# Schematic_v24.net
KiCad netlist of a schematic drawn in EAGLE
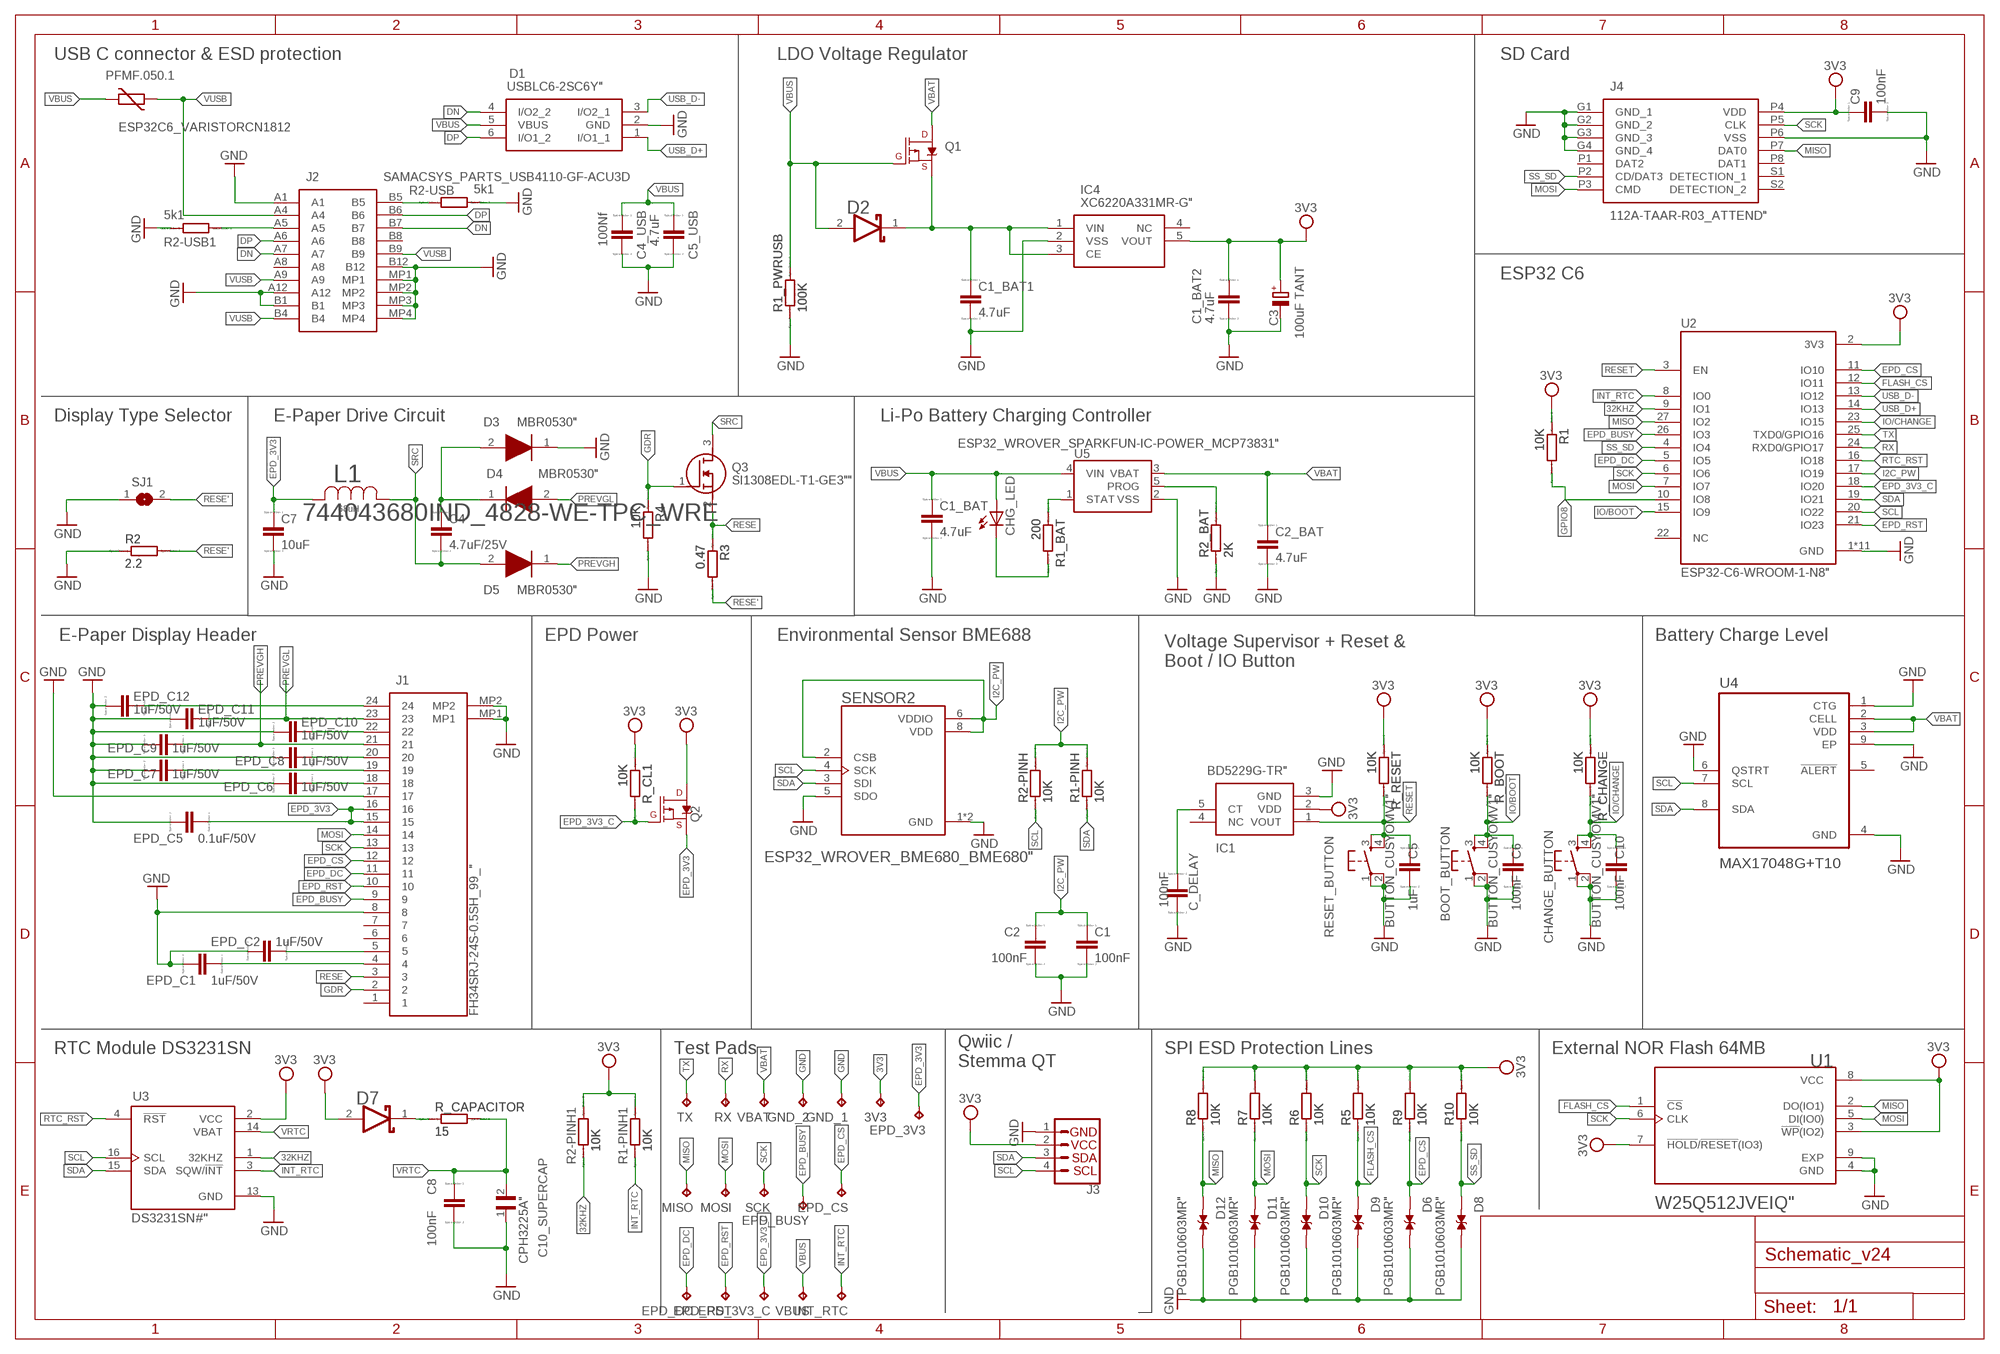
[diagram p0: schematic, sheet 1]

(export (version "E")
  (design (tool "Eeschema 10.0.6"))
  (components
    (comp (ref "3V3")
      (value "TPTP20R")
      (footprint "eagle-import:TP20R")
      (libsource (lib "eagle-import") (part "TPTP20R"))
    )
    (comp (ref "BOOT_BUTTON")
      (value "BUTTON_CUSYOMV1\"")
      (footprint "eagle-import:MYBUTTON")
      (libsource (lib "eagle-import") (part "BUTTON_CUSYOMV1{dblquote}"))
    )
    (comp (ref "C1")
      (value "100nF")
      (footprint "eagle-import:ESP32_WROVER_EAGLE-LTSPICE_C0402")
      (libsource (lib "eagle-import") (part "ESP32_WROVER_EAGLE-LTSPICE_CC0402"))
    )
    (comp (ref "C1_BAT")
      (value "4.7uF")
      (footprint "eagle-import:ESP32_WROVER_EAGLE-LTSPICE_C0402")
      (libsource (lib "eagle-import") (part "ESP32_WROVER_EAGLE-LTSPICE_CC0402"))
    )
    (comp (ref "C1_BAT1")
      (value "4.7uF")
      (footprint "eagle-import:EAGLE-LTSPICE_C0402")
      (libsource (lib "eagle-import") (part "EAGLE-LTSPICE_CC0402"))
    )
    (comp (ref "C1_BAT2")
      (value "4.7uF")
      (footprint "eagle-import:EAGLE-LTSPICE_C0402")
      (libsource (lib "eagle-import") (part "EAGLE-LTSPICE_CC0402"))
    )
    (comp (ref "C2")
      (value "100nF")
      (footprint "eagle-import:ESP32_WROVER_EAGLE-LTSPICE_C0402")
      (libsource (lib "eagle-import") (part "ESP32_WROVER_EAGLE-LTSPICE_CC0402"))
    )
    (comp (ref "C2_BAT")
      (value "4.7uF")
      (footprint "eagle-import:ESP32_WROVER_EAGLE-LTSPICE_C0402")
      (libsource (lib "eagle-import") (part "ESP32_WROVER_EAGLE-LTSPICE_CC0402"))
    )
    (comp (ref "C3")
      (value "100uF TANT")
      (footprint "eagle-import:RCL_CT3528")
      (libsource (lib "eagle-import") (part "RCL_CPOL-EUCT3528"))
    )
    (comp (ref "C4")
      (value "4.7uF/25V")
      (footprint "eagle-import:ESP32_WROVER_EAGLE-LTSPICE_C0402")
      (libsource (lib "eagle-import") (part "ESP32_WROVER_EAGLE-LTSPICE_CC0402"))
    )
    (comp (ref "C4_USB")
      (value "100Nf")
      (footprint "eagle-import:ESP32_WROVER_EAGLE-LTSPICE_C0402")
      (libsource (lib "eagle-import") (part "ESP32_WROVER_EAGLE-LTSPICE_CC0402"))
    )
    (comp (ref "C5")
      (value "1uF")
      (footprint "eagle-import:ESP32_WROVER_EAGLE-LTSPICE_C0402")
      (libsource (lib "eagle-import") (part "ESP32_WROVER_EAGLE-LTSPICE_CC0402"))
    )
    (comp (ref "C5_USB")
      (value "4.7uF")
      (footprint "eagle-import:ESP32_WROVER_EAGLE-LTSPICE_C0402")
      (libsource (lib "eagle-import") (part "ESP32_WROVER_EAGLE-LTSPICE_CC0402"))
    )
    (comp (ref "C6")
      (value "100nF")
      (footprint "eagle-import:ESP32_WROVER_EAGLE-LTSPICE_C0402")
      (libsource (lib "eagle-import") (part "ESP32_WROVER_EAGLE-LTSPICE_CC0402"))
    )
    (comp (ref "C7")
      (value "10uF")
      (footprint "eagle-import:ESP32_WROVER_EAGLE-LTSPICE_C0402")
      (libsource (lib "eagle-import") (part "ESP32_WROVER_EAGLE-LTSPICE_CC0402"))
    )
    (comp (ref "C8")
      (value "100nF")
      (footprint "eagle-import:ESP32_WROVER_EAGLE-LTSPICE_C0402")
      (libsource (lib "eagle-import") (part "ESP32_WROVER_EAGLE-LTSPICE_CC0402"))
    )
    (comp (ref "C9")
      (value "100nF")
      (footprint "eagle-import:EAGLE-LTSPICE_C0402")
      (libsource (lib "eagle-import") (part "EAGLE-LTSPICE_CC0402"))
    )
    (comp (ref "C10")
      (value "100nF")
      (footprint "eagle-import:ESP32_WROVER_EAGLE-LTSPICE_C0402")
      (libsource (lib "eagle-import") (part "ESP32_WROVER_EAGLE-LTSPICE_CC0402"))
    )
    (comp (ref "C10_SUPERCAP")
      (value "CPH3225A\"")
      (footprint "eagle-import:CAPCP3225X100N")
      (libsource (lib "eagle-import") (part "CPH3225A{dblquote}"))
    )
    (comp (ref "CHANGE_BUTTON")
      (value "BUTTON_CUSYOMV1\"")
      (footprint "eagle-import:MYBUTTON")
      (libsource (lib "eagle-import") (part "BUTTON_CUSYOMV1{dblquote}"))
    )
    (comp (ref "CHG_LED")
      (value "ADAFRUIT_LEDCHIP-LED0603")
      (footprint "eagle-import:ADAFRUIT_CHIP-LED0603")
      (libsource (lib "eagle-import") (part "ADAFRUIT_LEDCHIP-LED0603"))
    )
    (comp (ref "C_DELAY")
      (value "100nF")
      (footprint "eagle-import:ESP32_WROVER_EAGLE-LTSPICE_C0402")
      (libsource (lib "eagle-import") (part "ESP32_WROVER_EAGLE-LTSPICE_CC0402"))
    )
    (comp (ref "D1")
      (value "USBLC6-2SC6Y\"")
      (footprint "eagle-import:SOT95P280X145-6N")
      (libsource (lib "eagle-import") (part "USBLC6-2SC6Y{dblquote}"))
    )
    (comp (ref "D2")
      (value "ESP32_WROVER_AVX---SD0805S020S1R0_AVX_SD0805S020S1R0_0_0AVX_SD0805S020S1R0_0_0")
      (footprint "eagle-import:ESP32_WROVER_AVX---SD0805S020S1R0_AVX_SD0805S020S1R0_0")
      (libsource (lib "eagle-import") (part "ESP32_WROVER_AVX---SD0805S020S1R0_AVX_SD0805S020S1R0_0_0AVX_SD0805S020S1R0_0_0"))
    )
    (comp (ref "D3")
      (value "MBR0530\"")
      (footprint "eagle-import:SOD3716X135N")
      (libsource (lib "eagle-import") (part "MBR0530{dblquote}"))
    )
    (comp (ref "D4")
      (value "MBR0530\"")
      (footprint "eagle-import:SOD3716X135N")
      (libsource (lib "eagle-import") (part "MBR0530{dblquote}"))
    )
    (comp (ref "D5")
      (value "MBR0530\"")
      (footprint "eagle-import:SOD3716X135N")
      (libsource (lib "eagle-import") (part "MBR0530{dblquote}"))
    )
    (comp (ref "D6")
      (value "PGB1010603MR\"")
      (footprint "eagle-import:DIOC1608X36N")
      (libsource (lib "eagle-import") (part "PGB1010603MR{dblquote}"))
    )
    (comp (ref "D7")
      (value "ESP32_WROVER_AVX---SD0805S020S1R0_AVX_SD0805S020S1R0_0_0AVX_SD0805S020S1R0_0_0")
      (footprint "eagle-import:ESP32_WROVER_AVX---SD0805S020S1R0_AVX_SD0805S020S1R0_0")
      (libsource (lib "eagle-import") (part "ESP32_WROVER_AVX---SD0805S020S1R0_AVX_SD0805S020S1R0_0_0AVX_SD0805S020S1R0_0_0"))
    )
    (comp (ref "D8")
      (value "PGB1010603MR\"")
      (footprint "eagle-import:DIOC1608X36N")
      (libsource (lib "eagle-import") (part "PGB1010603MR{dblquote}"))
    )
    (comp (ref "D9")
      (value "PGB1010603MR\"")
      (footprint "eagle-import:DIOC1608X36N")
      (libsource (lib "eagle-import") (part "PGB1010603MR{dblquote}"))
    )
    (comp (ref "D10")
      (value "PGB1010603MR\"")
      (footprint "eagle-import:DIOC1608X36N")
      (libsource (lib "eagle-import") (part "PGB1010603MR{dblquote}"))
    )
    (comp (ref "D11")
      (value "PGB1010603MR\"")
      (footprint "eagle-import:DIOC1608X36N")
      (libsource (lib "eagle-import") (part "PGB1010603MR{dblquote}"))
    )
    (comp (ref "D12")
      (value "PGB1010603MR\"")
      (footprint "eagle-import:DIOC1608X36N")
      (libsource (lib "eagle-import") (part "PGB1010603MR{dblquote}"))
    )
    (comp (ref "EPD_3V3")
      (value "TPTP20R")
      (footprint "eagle-import:TP20R")
      (libsource (lib "eagle-import") (part "TPTP20R"))
    )
    (comp (ref "EPD_3V3_C")
      (value "TPTP20R")
      (footprint "eagle-import:TP20R")
      (libsource (lib "eagle-import") (part "TPTP20R"))
    )
    (comp (ref "EPD_BUSY")
      (value "TPTP20R")
      (footprint "eagle-import:TP20R")
      (libsource (lib "eagle-import") (part "TPTP20R"))
    )
    (comp (ref "EPD_C1")
      (value "1uF/50V")
      (footprint "eagle-import:ESP32_WROVER_EAGLE-LTSPICE_C0402")
      (libsource (lib "eagle-import") (part "ESP32_WROVER_EAGLE-LTSPICE_CC0402"))
    )
    (comp (ref "EPD_C2")
      (value "1uF/50V")
      (footprint "eagle-import:ESP32_WROVER_EAGLE-LTSPICE_C0402")
      (libsource (lib "eagle-import") (part "ESP32_WROVER_EAGLE-LTSPICE_CC0402"))
    )
    (comp (ref "EPD_C5")
      (value "0.1uF/50V")
      (footprint "eagle-import:ESP32_WROVER_EAGLE-LTSPICE_C0402")
      (libsource (lib "eagle-import") (part "ESP32_WROVER_EAGLE-LTSPICE_CC0402"))
    )
    (comp (ref "EPD_C6")
      (value "1uF/50V")
      (footprint "eagle-import:ESP32_WROVER_EAGLE-LTSPICE_C0402")
      (libsource (lib "eagle-import") (part "ESP32_WROVER_EAGLE-LTSPICE_CC0402"))
    )
    (comp (ref "EPD_C7")
      (value "1uF/50V")
      (footprint "eagle-import:ESP32_WROVER_EAGLE-LTSPICE_C0402")
      (libsource (lib "eagle-import") (part "ESP32_WROVER_EAGLE-LTSPICE_CC0402"))
    )
    (comp (ref "EPD_C8")
      (value "1uF/50V")
      (footprint "eagle-import:ESP32_WROVER_EAGLE-LTSPICE_C0402")
      (libsource (lib "eagle-import") (part "ESP32_WROVER_EAGLE-LTSPICE_CC0402"))
    )
    (comp (ref "EPD_C9")
      (value "1uF/50V")
      (footprint "eagle-import:ESP32_WROVER_EAGLE-LTSPICE_C0402")
      (libsource (lib "eagle-import") (part "ESP32_WROVER_EAGLE-LTSPICE_CC0402"))
    )
    (comp (ref "EPD_C10")
      (value "1uF/50V")
      (footprint "eagle-import:ESP32_WROVER_EAGLE-LTSPICE_C0402")
      (libsource (lib "eagle-import") (part "ESP32_WROVER_EAGLE-LTSPICE_CC0402"))
    )
    (comp (ref "EPD_C11")
      (value "1uF/50V")
      (footprint "eagle-import:ESP32_WROVER_EAGLE-LTSPICE_C0402")
      (libsource (lib "eagle-import") (part "ESP32_WROVER_EAGLE-LTSPICE_CC0402"))
    )
    (comp (ref "EPD_C12")
      (value "1uF/50V")
      (footprint "eagle-import:ESP32_WROVER_EAGLE-LTSPICE_C0402")
      (libsource (lib "eagle-import") (part "ESP32_WROVER_EAGLE-LTSPICE_CC0402"))
    )
    (comp (ref "EPD_CS")
      (value "TPTP20R")
      (footprint "eagle-import:TP20R")
      (libsource (lib "eagle-import") (part "TPTP20R"))
    )
    (comp (ref "EPD_DC")
      (value "TPTP20R")
      (footprint "eagle-import:TP20R")
      (libsource (lib "eagle-import") (part "TPTP20R"))
    )
    (comp (ref "EPD_RST")
      (value "TPTP20R")
      (footprint "eagle-import:TP20R")
      (libsource (lib "eagle-import") (part "TPTP20R"))
    )
    (comp (ref "GND_1")
      (value "TPTP20R")
      (footprint "eagle-import:TP20R")
      (libsource (lib "eagle-import") (part "TPTP20R"))
    )
    (comp (ref "GND_2")
      (value "TPTP20R")
      (footprint "eagle-import:TP20R")
      (libsource (lib "eagle-import") (part "TPTP20R"))
    )
    (comp (ref "IC1")
      (value "BD5229G-TR\"")
      (footprint "eagle-import:SOT95P280X125-5N")
      (libsource (lib "eagle-import") (part "BD5229G-TR{dblquote}"))
    )
    (comp (ref "IC4")
      (value "XC6220A331MR-G\"")
      (footprint "eagle-import:SOT95P280X120-5N")
      (libsource (lib "eagle-import") (part "XC6220A331MR-G{dblquote}"))
    )
    (comp (ref "INT_RTC")
      (value "TPTP20R")
      (footprint "eagle-import:TP20R")
      (libsource (lib "eagle-import") (part "TPTP20R"))
    )
    (comp (ref "J1")
      (value "FH34SRJ-24S-0.5SH_99_\"")
      (footprint "eagle-import:FH34SRJ24S05SH99")
      (libsource (lib "eagle-import") (part "FH34SRJ-24S-0.5SH_99_{dblquote}"))
    )
    (comp (ref "J2")
      (value "SAMACSYS_PARTS_USB4110-GF-ACU3D")
      (footprint "eagle-import:SAMACSYS_PARTS_USB4110GFA")
      (libsource (lib "eagle-import") (part "SAMACSYS_PARTS_USB4110-GF-ACU3D"))
    )
    (comp (ref "J3")
      (value "QWIIC_RIGHT_ANGLE")
      (footprint "eagle-import:JST04_1MM_RA")
      (libsource (lib "eagle-import") (part "QWIIC_CONNECTORJS-1MM"))
    )
    (comp (ref "J4")
      (value "112A-TAAR-R03_ATTEND\"")
      (footprint "eagle-import:112ATAARR03ATTEND")
      (libsource (lib "eagle-import") (part "112A-TAAR-R03_ATTEND{dblquote}"))
    )
    (comp (ref "L1")
      (value "744043680IND_4828-WE-TPC_WRE")
      (footprint "eagle-import:IND_4828-WE-TPC_WRE")
      (fields (field (name "VAL") "68uH"))
      (libsource (lib "eagle-import") (part "744043680IND_4828-WE-TPC_WRE"))
    )
    (comp (ref "MISO")
      (value "TPTP20R")
      (footprint "eagle-import:TP20R")
      (libsource (lib "eagle-import") (part "TPTP20R"))
    )
    (comp (ref "MOSI")
      (value "TPTP20R")
      (footprint "eagle-import:TP20R")
      (libsource (lib "eagle-import") (part "TPTP20R"))
    )
    (comp (ref "PFMF.050.1")
      (value "ESP32C6_VARISTORCN1812")
      (footprint "eagle-import:ESP32C6_VARISTOR_CT_CN1812")
      (libsource (lib "eagle-import") (part "ESP32C6_VARISTORCN1812"))
    )
    (comp (ref "Q1")
      (value "20V/4.2A/52mΩ/1.4W")
      (footprint "eagle-import:ESP32_WROVER_SPARKFUN-DISCRETESEMI_SOT23-3")
      (libsource (lib "eagle-import") (part "ESP32_WROVER_SPARKFUN-DISCRETESEMI_MOSFET_PCH-DMG2305UX-7"))
    )
    (comp (ref "Q2")
      (value "20V/4.2A/52mΩ/1.4W")
      (footprint "eagle-import:ESP32_WROVER_SPARKFUN-DISCRETESEMI_SOT23-3")
      (libsource (lib "eagle-import") (part "ESP32_WROVER_SPARKFUN-DISCRETESEMI_MOSFET_PCH-DMG2305UX-7"))
    )
    (comp (ref "Q3")
      (value "SI1308EDL-T1-GE3\"\"")
      (footprint "eagle-import:SOT65P210X110-3N")
      (libsource (lib "eagle-import") (part "SI1308EDL-T1-GE3{dblquote}{dblquote}"))
    )
    (comp (ref "R1")
      (value "10K")
      (footprint "eagle-import:ESP32_WROVER_EAGLE-LTSPICE_R0402")
      (libsource (lib "eagle-import") (part "ESP32_WROVER_EAGLE-LTSPICE_RR0402"))
    )
    (comp (ref "R1-PINH")
      (value "10K")
      (footprint "eagle-import:ESP32_WROVER_EAGLE-LTSPICE_R0402")
      (libsource (lib "eagle-import") (part "ESP32_WROVER_EAGLE-LTSPICE_RR0402"))
    )
    (comp (ref "R1-PINH1")
      (value "10K")
      (footprint "eagle-import:ESP32_WROVER_EAGLE-LTSPICE_R0402")
      (libsource (lib "eagle-import") (part "ESP32_WROVER_EAGLE-LTSPICE_RR0402"))
    )
    (comp (ref "R1_BAT")
      (value "200")
      (footprint "eagle-import:ESP32_WROVER_EAGLE-LTSPICE_R0402")
      (libsource (lib "eagle-import") (part "ESP32_WROVER_EAGLE-LTSPICE_RR0402"))
    )
    (comp (ref "R1_PWRUSB")
      (value "100K")
      (footprint "eagle-import:ESP32_WROVER_EAGLE-LTSPICE_R0402")
      (libsource (lib "eagle-import") (part "ESP32_WROVER_EAGLE-LTSPICE_RR0402"))
    )
    (comp (ref "R2")
      (value "2.2")
      (footprint "eagle-import:ESP32_WROVER_EAGLE-LTSPICE_R0402")
      (libsource (lib "eagle-import") (part "ESP32_WROVER_EAGLE-LTSPICE_RR0402"))
    )
    (comp (ref "R2-PINH")
      (value "10K")
      (footprint "eagle-import:ESP32_WROVER_EAGLE-LTSPICE_R0402")
      (libsource (lib "eagle-import") (part "ESP32_WROVER_EAGLE-LTSPICE_RR0402"))
    )
    (comp (ref "R2-PINH1")
      (value "10K")
      (footprint "eagle-import:ESP32_WROVER_EAGLE-LTSPICE_R0402")
      (libsource (lib "eagle-import") (part "ESP32_WROVER_EAGLE-LTSPICE_RR0402"))
    )
    (comp (ref "R2-USB")
      (value "5k1")
      (footprint "eagle-import:ESP32_WROVER_EAGLE-LTSPICE_R0402")
      (libsource (lib "eagle-import") (part "ESP32_WROVER_EAGLE-LTSPICE_RR0402"))
    )
    (comp (ref "R2-USB1")
      (value "5k1")
      (footprint "eagle-import:ESP32_WROVER_EAGLE-LTSPICE_R0402")
      (libsource (lib "eagle-import") (part "ESP32_WROVER_EAGLE-LTSPICE_RR0402"))
    )
    (comp (ref "R2_BAT")
      (value "2K")
      (footprint "eagle-import:ESP32_WROVER_EAGLE-LTSPICE_R0402")
      (libsource (lib "eagle-import") (part "ESP32_WROVER_EAGLE-LTSPICE_RR0402"))
    )
    (comp (ref "R3")
      (value "0.47")
      (footprint "eagle-import:ESP32_WROVER_EAGLE-LTSPICE_R0402")
      (libsource (lib "eagle-import") (part "ESP32_WROVER_EAGLE-LTSPICE_RR0402"))
    )
    (comp (ref "R4")
      (value "10K")
      (footprint "eagle-import:ESP32_WROVER_EAGLE-LTSPICE_R0402")
      (libsource (lib "eagle-import") (part "ESP32_WROVER_EAGLE-LTSPICE_RR0402"))
    )
    (comp (ref "R5")
      (value "10K")
      (footprint "eagle-import:ESP32_WROVER_EAGLE-LTSPICE_R0402")
      (libsource (lib "eagle-import") (part "ESP32_WROVER_EAGLE-LTSPICE_RR0402"))
    )
    (comp (ref "R6")
      (value "10K")
      (footprint "eagle-import:ESP32_WROVER_EAGLE-LTSPICE_R0402")
      (libsource (lib "eagle-import") (part "ESP32_WROVER_EAGLE-LTSPICE_RR0402"))
    )
    (comp (ref "R7")
      (value "10K")
      (footprint "eagle-import:ESP32_WROVER_EAGLE-LTSPICE_R0402")
      (libsource (lib "eagle-import") (part "ESP32_WROVER_EAGLE-LTSPICE_RR0402"))
    )
    (comp (ref "R8")
      (value "10K")
      (footprint "eagle-import:ESP32_WROVER_EAGLE-LTSPICE_R0402")
      (libsource (lib "eagle-import") (part "ESP32_WROVER_EAGLE-LTSPICE_RR0402"))
    )
    (comp (ref "R9")
      (value "10K")
      (footprint "eagle-import:ESP32_WROVER_EAGLE-LTSPICE_R0402")
      (libsource (lib "eagle-import") (part "ESP32_WROVER_EAGLE-LTSPICE_RR0402"))
    )
    (comp (ref "R10")
      (value "10K")
      (footprint "eagle-import:ESP32_WROVER_EAGLE-LTSPICE_R0402")
      (libsource (lib "eagle-import") (part "ESP32_WROVER_EAGLE-LTSPICE_RR0402"))
    )
    (comp (ref "RESET_BUTTON")
      (value "BUTTON_CUSYOMV1\"")
      (footprint "eagle-import:MYBUTTON")
      (libsource (lib "eagle-import") (part "BUTTON_CUSYOMV1{dblquote}"))
    )
    (comp (ref "RX")
      (value "TPTP20R")
      (footprint "eagle-import:TP20R")
      (libsource (lib "eagle-import") (part "TPTP20R"))
    )
    (comp (ref "R_BOOT")
      (value "10K")
      (footprint "eagle-import:ESP32_WROVER_EAGLE-LTSPICE_R0402")
      (libsource (lib "eagle-import") (part "ESP32_WROVER_EAGLE-LTSPICE_RR0402"))
    )
    (comp (ref "R_CAPACITOR")
      (value "15")
      (footprint "eagle-import:ESP32_WROVER_EAGLE-LTSPICE_R0402")
      (libsource (lib "eagle-import") (part "ESP32_WROVER_EAGLE-LTSPICE_RR0402"))
    )
    (comp (ref "R_CHANGE")
      (value "10K")
      (footprint "eagle-import:ESP32_WROVER_EAGLE-LTSPICE_R0402")
      (libsource (lib "eagle-import") (part "ESP32_WROVER_EAGLE-LTSPICE_RR0402"))
    )
    (comp (ref "R_CL1")
      (value "10K")
      (footprint "eagle-import:ESP32_WROVER_EAGLE-LTSPICE_R0402")
      (libsource (lib "eagle-import") (part "ESP32_WROVER_EAGLE-LTSPICE_RR0402"))
    )
    (comp (ref "R_RESET")
      (value "10K")
      (footprint "eagle-import:ESP32_WROVER_EAGLE-LTSPICE_R0402")
      (libsource (lib "eagle-import") (part "ESP32_WROVER_EAGLE-LTSPICE_RR0402"))
    )
    (comp (ref "SCK")
      (value "TPTP20R")
      (footprint "eagle-import:TP20R")
      (libsource (lib "eagle-import") (part "TPTP20R"))
    )
    (comp (ref "SENSOR2")
      (value "ESP32_WROVER_BME680_BME680\"")
      (footprint "eagle-import:ESP32_WROVER_BME680_PSON80P300X300X100-8N")
      (libsource (lib "eagle-import") (part "ESP32_WROVER_BME680_BME680{dblquote}"))
    )
    (comp (ref "SJ1")
      (value "SJ\"\"")
      (footprint "eagle-import:SJ")
      (libsource (lib "eagle-import") (part "SJ{dblquote}{dblquote}"))
    )
    (comp (ref "TX")
      (value "TPTP20R")
      (footprint "eagle-import:TP20R")
      (libsource (lib "eagle-import") (part "TPTP20R"))
    )
    (comp (ref "U1")
      (value "W25Q512JVEIQ\"")
      (footprint "eagle-import:SON127P600X800X80-9N")
      (libsource (lib "eagle-import") (part "W25Q512JVEIQ{dblquote}"))
    )
    (comp (ref "U2")
      (value "ESP32-C6-WROOM-1-N8\"")
      (footprint "eagle-import:XCVR_ESP32-C6-WROOM-1-N8")
      (libsource (lib "eagle-import") (part "ESP32-C6-WROOM-1-N8{dblquote}"))
    )
    (comp (ref "U3")
      (value "DS3231SN#\"")
      (footprint "eagle-import:SOIC127P1032X265-16N")
      (libsource (lib "eagle-import") (part "DS3231SN#{dblquote}"))
    )
    (comp (ref "U4")
      (value "MAX17048G+T10")
      (footprint "eagle-import:SON50P200X200X80-9N")
      (libsource (lib "eagle-import") (part "MAX17048G+T10{dblquote}"))
    )
    (comp (ref "U5")
      (value "ESP32_WROVER_SPARKFUN-IC-POWER_MCP73831\"")
      (footprint "eagle-import:ESP32_WROVER_SPARKFUN-IC-POWER_SOT23-5")
      (libsource (lib "eagle-import") (part "ESP32_WROVER_SPARKFUN-IC-POWER_MCP73831{dblquote}"))
    )
    (comp (ref "VBAT")
      (value "TPTP20R")
      (footprint "eagle-import:TP20R")
      (libsource (lib "eagle-import") (part "TPTP20R"))
    )
    (comp (ref "VBUS")
      (value "TPTP20R")
      (footprint "eagle-import:TP20R")
      (libsource (lib "eagle-import") (part "TPTP20R"))
    )
  )
  (nets
    (net (code "1") (name "3V3") (class "Default")
      (node (ref "3V3") (pin "TP") (pinfunction "TP_TP") (pintype "input"))
      (node (ref "C1_BAT2") (pin "1") (pinfunction "1_1") (pintype "passive"))
      (node (ref "C3") (pin "+") (pinfunction "+_+") (pintype "passive"))
      (node (ref "C9") (pin "1") (pinfunction "1_1") (pintype "passive"))
      (node (ref "D7") (pin "2") (pinfunction "ANODE_2") (pintype "bidirectional"))
      (node (ref "IC1") (pin "2") (pinfunction "VDD_2") (pintype "bidirectional"))
      (node (ref "IC4") (pin "5") (pinfunction "VOUT_5") (pintype "bidirectional"))
      (node (ref "J3") (pin "2") (pinfunction "2_2") (pintype "power_in"))
      (node (ref "J4") (pin "P4") (pinfunction "VDD_P4") (pintype "bidirectional"))
      (node (ref "Q2") (pin "3") (pinfunction "D_3") (pintype "bidirectional"))
      (node (ref "R1") (pin "1") (pinfunction "1_1") (pintype "passive"))
      (node (ref "R1-PINH1") (pin "2") (pinfunction "2_2") (pintype "passive"))
      (node (ref "R10") (pin "2") (pinfunction "2_2") (pintype "passive"))
      (node (ref "R2-PINH1") (pin "2") (pinfunction "2_2") (pintype "passive"))
      (node (ref "R5") (pin "2") (pinfunction "2_2") (pintype "passive"))
      (node (ref "R6") (pin "2") (pinfunction "2_2") (pintype "passive"))
      (node (ref "R7") (pin "2") (pinfunction "2_2") (pintype "passive"))
      (node (ref "R8") (pin "2") (pinfunction "2_2") (pintype "passive"))
      (node (ref "R9") (pin "2") (pinfunction "2_2") (pintype "passive"))
      (node (ref "R_BOOT") (pin "1") (pinfunction "1_1") (pintype "passive"))
      (node (ref "R_CHANGE") (pin "1") (pinfunction "1_1") (pintype "passive"))
      (node (ref "R_CL1") (pin "1") (pinfunction "1_1") (pintype "passive"))
      (node (ref "R_RESET") (pin "1") (pinfunction "1_1") (pintype "passive"))
      (node (ref "U1") (pin "3") (pinfunction "~{WP}(IO2)_3") (pintype "bidirectional"))
      (node (ref "U1") (pin "7") (pinfunction "~{HOLD}/~{RESET}(IO3)_7") (pintype "bidirectional"))
      (node (ref "U1") (pin "8") (pinfunction "VCC_8") (pintype "power_in"))
      (node (ref "U2") (pin "2") (pinfunction "3V3_2") (pintype "power_in"))
      (node (ref "U3") (pin "2") (pinfunction "VCC_2") (pintype "power_in"))
    )
    (net (code "2") (name "32KHZ") (class "Default")
      (node (ref "R2-PINH1") (pin "1") (pinfunction "1_1") (pintype "passive"))
      (node (ref "U2") (pin "9") (pinfunction "IO1_9") (pintype "bidirectional"))
      (node (ref "U3") (pin "1") (pinfunction "32KHZ_1") (pintype "output"))
    )
    (net (code "3") (name "DN") (class "Default")
      (node (ref "D1") (pin "4") (pinfunction "I/O2_2_4") (pintype "bidirectional"))
      (node (ref "J2") (pin "A7") (pinfunction "A7_A7") (pintype "bidirectional"))
      (node (ref "J2") (pin "B7") (pinfunction "B7_B7") (pintype "bidirectional"))
    )
    (net (code "4") (name "DP") (class "Default")
      (node (ref "D1") (pin "6") (pinfunction "I/O1_2_6") (pintype "bidirectional"))
      (node (ref "J2") (pin "A6") (pinfunction "A6_A6") (pintype "bidirectional"))
      (node (ref "J2") (pin "B6") (pinfunction "B6_B6") (pintype "bidirectional"))
    )
    (net (code "5") (name "EPD_3V3") (class "Default")
      (node (ref "C7") (pin "1") (pinfunction "1_1") (pintype "passive"))
      (node (ref "EPD_3V3") (pin "TP") (pinfunction "TP_TP") (pintype "input"))
      (node (ref "EPD_C5") (pin "1") (pinfunction "1_1") (pintype "passive"))
      (node (ref "J1") (pin "15") (pinfunction "15_15") (pintype "bidirectional"))
      (node (ref "J1") (pin "16") (pinfunction "16_16") (pintype "bidirectional"))
      (node (ref "L1") (pin "2") (pinfunction "2_2") (pintype "passive"))
      (node (ref "Q2") (pin "2") (pinfunction "S_2") (pintype "bidirectional"))
    )
    (net (code "6") (name "EPD_3V3_C") (class "Default")
      (node (ref "EPD_3V3_C") (pin "TP") (pinfunction "TP_TP") (pintype "input"))
      (node (ref "Q2") (pin "1") (pinfunction "G_1") (pintype "bidirectional"))
      (node (ref "R_CL1") (pin "2") (pinfunction "2_2") (pintype "passive"))
      (node (ref "U2") (pin "18") (pinfunction "IO20_18") (pintype "bidirectional"))
    )
    (net (code "7") (name "EPD_BUSY") (class "Default")
      (node (ref "EPD_BUSY") (pin "TP") (pinfunction "TP_TP") (pintype "input"))
      (node (ref "J1") (pin "9") (pinfunction "9_9") (pintype "bidirectional"))
      (node (ref "U2") (pin "26") (pinfunction "IO3_26") (pintype "bidirectional"))
    )
    (net (code "8") (name "EPD_CS") (class "Default")
      (node (ref "D6") (pin "1") (pinfunction "1_1") (pintype "passive"))
      (node (ref "EPD_CS") (pin "TP") (pinfunction "TP_TP") (pintype "input"))
      (node (ref "J1") (pin "12") (pinfunction "12_12") (pintype "bidirectional"))
      (node (ref "R9") (pin "1") (pinfunction "1_1") (pintype "passive"))
      (node (ref "U2") (pin "11") (pinfunction "IO10_11") (pintype "bidirectional"))
    )
    (net (code "9") (name "EPD_DC") (class "Default")
      (node (ref "EPD_DC") (pin "TP") (pinfunction "TP_TP") (pintype "input"))
      (node (ref "J1") (pin "11") (pinfunction "11_11") (pintype "bidirectional"))
      (node (ref "U2") (pin "5") (pinfunction "IO5_5") (pintype "bidirectional"))
    )
    (net (code "10") (name "EPD_RST") (class "Default")
      (node (ref "EPD_RST") (pin "TP") (pinfunction "TP_TP") (pintype "input"))
      (node (ref "J1") (pin "10") (pinfunction "10_10") (pintype "bidirectional"))
      (node (ref "U2") (pin "21") (pinfunction "IO23_21") (pintype "bidirectional"))
    )
    (net (code "11") (name "FLASH_CS") (class "Default")
      (node (ref "D9") (pin "1") (pinfunction "1_1") (pintype "passive"))
      (node (ref "R5") (pin "1") (pinfunction "1_1") (pintype "passive"))
      (node (ref "U1") (pin "1") (pinfunction "~{CS}_1") (pintype "input"))
      (node (ref "U2") (pin "12") (pinfunction "IO11_12") (pintype "bidirectional"))
    )
    (net (code "12") (name "GDR") (class "Default")
      (node (ref "J1") (pin "2") (pinfunction "2_2") (pintype "bidirectional"))
      (node (ref "Q3") (pin "1") (pinfunction "G_1") (pintype "bidirectional"))
      (node (ref "R4") (pin "1") (pinfunction "1_1") (pintype "passive"))
    )
    (net (code "13") (name "GND") (class "Default")
      (node (ref "BOOT_BUTTON") (pin "1") (pinfunction "1_1") (pintype "passive"))
      (node (ref "BOOT_BUTTON") (pin "2") (pinfunction "2_2") (pintype "passive"))
      (node (ref "C1") (pin "2") (pinfunction "2_2") (pintype "passive"))
      (node (ref "C10") (pin "2") (pinfunction "2_2") (pintype "passive"))
      (node (ref "C10_SUPERCAP") (pin "1") (pinfunction "1_1") (pintype "passive"))
      (node (ref "C1_BAT") (pin "2") (pinfunction "2_2") (pintype "passive"))
      (node (ref "C1_BAT1") (pin "2") (pinfunction "2_2") (pintype "passive"))
      (node (ref "C1_BAT2") (pin "2") (pinfunction "2_2") (pintype "passive"))
      (node (ref "C2") (pin "2") (pinfunction "2_2") (pintype "passive"))
      (node (ref "C2_BAT") (pin "2") (pinfunction "2_2") (pintype "passive"))
      (node (ref "C3") (pin "-") (pinfunction "-_-") (pintype "passive"))
      (node (ref "C4_USB") (pin "2") (pinfunction "2_2") (pintype "passive"))
      (node (ref "C5") (pin "2") (pinfunction "2_2") (pintype "passive"))
      (node (ref "C5_USB") (pin "2") (pinfunction "2_2") (pintype "passive"))
      (node (ref "C6") (pin "2") (pinfunction "2_2") (pintype "passive"))
      (node (ref "C7") (pin "2") (pinfunction "2_2") (pintype "passive"))
      (node (ref "C8") (pin "2") (pinfunction "2_2") (pintype "passive"))
      (node (ref "C9") (pin "2") (pinfunction "2_2") (pintype "passive"))
      (node (ref "CHANGE_BUTTON") (pin "1") (pinfunction "1_1") (pintype "passive"))
      (node (ref "CHANGE_BUTTON") (pin "2") (pinfunction "2_2") (pintype "passive"))
      (node (ref "C_DELAY") (pin "2") (pinfunction "2_2") (pintype "passive"))
      (node (ref "D1") (pin "2") (pinfunction "GND_2") (pintype "bidirectional"))
      (node (ref "D10") (pin "2") (pinfunction "2_2") (pintype "passive"))
      (node (ref "D11") (pin "2") (pinfunction "2_2") (pintype "passive"))
      (node (ref "D12") (pin "2") (pinfunction "2_2") (pintype "passive"))
      (node (ref "D3") (pin "1") (pinfunction "K_1") (pintype "bidirectional"))
      (node (ref "D6") (pin "2") (pinfunction "2_2") (pintype "passive"))
      (node (ref "D8") (pin "2") (pinfunction "2_2") (pintype "passive"))
      (node (ref "D9") (pin "2") (pinfunction "2_2") (pintype "passive"))
      (node (ref "EPD_C1") (pin "2") (pinfunction "2_2") (pintype "passive"))
      (node (ref "EPD_C10") (pin "2") (pinfunction "2_2") (pintype "passive"))
      (node (ref "EPD_C11") (pin "2") (pinfunction "2_2") (pintype "passive"))
      (node (ref "EPD_C12") (pin "2") (pinfunction "2_2") (pintype "passive"))
      (node (ref "EPD_C2") (pin "2") (pinfunction "2_2") (pintype "passive"))
      (node (ref "EPD_C5") (pin "2") (pinfunction "2_2") (pintype "passive"))
      (node (ref "EPD_C6") (pin "2") (pinfunction "2_2") (pintype "passive"))
      (node (ref "EPD_C7") (pin "2") (pinfunction "2_2") (pintype "passive"))
      (node (ref "EPD_C8") (pin "2") (pinfunction "2_2") (pintype "passive"))
      (node (ref "EPD_C9") (pin "2") (pinfunction "2_2") (pintype "passive"))
      (node (ref "GND_1") (pin "TP") (pinfunction "TP_TP") (pintype "input"))
      (node (ref "GND_2") (pin "TP") (pinfunction "TP_TP") (pintype "input"))
      (node (ref "IC1") (pin "3") (pinfunction "GND_3") (pintype "bidirectional"))
      (node (ref "IC4") (pin "2") (pinfunction "VSS_2") (pintype "bidirectional"))
      (node (ref "J1") (pin "17") (pinfunction "17_17") (pintype "bidirectional"))
      (node (ref "J1") (pin "8") (pinfunction "8_8") (pintype "bidirectional"))
      (node (ref "J1") (pin "MP1") (pinfunction "MP1_MP1") (pintype "bidirectional"))
      (node (ref "J1") (pin "MP2") (pinfunction "MP2_MP2") (pintype "bidirectional"))
      (node (ref "J2") (pin "A1") (pinfunction "A1_A1") (pintype "bidirectional"))
      (node (ref "J2") (pin "A12") (pinfunction "A12_A12") (pintype "bidirectional"))
      (node (ref "J2") (pin "B1") (pinfunction "B1_B1") (pintype "bidirectional"))
      (node (ref "J2") (pin "B12") (pinfunction "B12_B12") (pintype "bidirectional"))
      (node (ref "J2") (pin "MP1") (pinfunction "MP1_MP1") (pintype "bidirectional"))
      (node (ref "J2") (pin "MP2") (pinfunction "MP2_MP2") (pintype "bidirectional"))
      (node (ref "J2") (pin "MP3") (pinfunction "MP3_MP3") (pintype "bidirectional"))
      (node (ref "J2") (pin "MP4") (pinfunction "MP4_MP4") (pintype "bidirectional"))
      (node (ref "J3") (pin "1") (pinfunction "1_1") (pintype "power_in"))
      (node (ref "J4") (pin "G1") (pinfunction "GND_1_G1") (pintype "bidirectional"))
      (node (ref "J4") (pin "G2") (pinfunction "GND_2_G2") (pintype "bidirectional"))
      (node (ref "J4") (pin "G3") (pinfunction "GND_3_G3") (pintype "bidirectional"))
      (node (ref "J4") (pin "G4") (pinfunction "GND_4_G4") (pintype "bidirectional"))
      (node (ref "J4") (pin "P6") (pinfunction "VSS_P6") (pintype "bidirectional"))
      (node (ref "R1_PWRUSB") (pin "1") (pinfunction "1_1") (pintype "passive"))
      (node (ref "R2") (pin "1") (pinfunction "1_1") (pintype "passive"))
      (node (ref "R2-USB") (pin "2") (pinfunction "2_2") (pintype "passive"))
      (node (ref "R2-USB1") (pin "1") (pinfunction "1_1") (pintype "passive"))
      (node (ref "R2_BAT") (pin "1") (pinfunction "1_1") (pintype "passive"))
      (node (ref "R4") (pin "2") (pinfunction "2_2") (pintype "passive"))
      (node (ref "RESET_BUTTON") (pin "1") (pinfunction "1_1") (pintype "passive"))
      (node (ref "RESET_BUTTON") (pin "2") (pinfunction "2_2") (pintype "passive"))
      (node (ref "SENSOR2") (pin "1") (pinfunction "GND_1") (pintype "power_in"))
      (node (ref "SENSOR2") (pin "5") (pinfunction "SDO_5") (pintype "bidirectional"))
      (node (ref "SENSOR2") (pin "7") (pinfunction "GND_7") (pintype "power_in"))
      (node (ref "SJ1") (pin "1") (pinfunction "1_1") (pintype "passive"))
      (node (ref "U1") (pin "4") (pinfunction "GND_4") (pintype "power_in"))
      (node (ref "U1") (pin "9") (pinfunction "EXP_9") (pintype "passive"))
      (node (ref "U2") (pin "1") (pinfunction "GND_1") (pintype "power_in"))
      (node (ref "U2") (pin "28") (pinfunction "GND_28") (pintype "power_in"))
      (node (ref "U2") (pin "29_1") (pinfunction "GND_29_1") (pintype "power_in"))
      (node (ref "U2") (pin "29_2") (pinfunction "GND_29_2") (pintype "power_in"))
      (node (ref "U2") (pin "29_3") (pinfunction "GND_29_3") (pintype "power_in"))
      (node (ref "U2") (pin "29_4") (pinfunction "GND_29_4") (pintype "power_in"))
      (node (ref "U2") (pin "29_5") (pinfunction "GND_29_5") (pintype "power_in"))
      (node (ref "U2") (pin "29_6") (pinfunction "GND_29_6") (pintype "power_in"))
      (node (ref "U2") (pin "29_7") (pinfunction "GND_29_7") (pintype "power_in"))
      (node (ref "U2") (pin "29_8") (pinfunction "GND_29_8") (pintype "power_in"))
      (node (ref "U2") (pin "29_9") (pinfunction "GND_29_9") (pintype "power_in"))
      (node (ref "U3") (pin "13") (pinfunction "GND_13") (pintype "power_in"))
      (node (ref "U4") (pin "1") (pinfunction "CTG_1") (pintype "power_in"))
      (node (ref "U4") (pin "4") (pinfunction "GND_4") (pintype "power_in"))
      (node (ref "U4") (pin "6") (pinfunction "QSTRT_6") (pintype "input"))
      (node (ref "U4") (pin "9") (pinfunction "EP_9") (pintype "power_in"))
      (node (ref "U5") (pin "2") (pinfunction "VSS_2") (pintype "power_in"))
    )
    (net (code "14") (name "GPIO8") (class "Default")
      (node (ref "R1") (pin "2") (pinfunction "2_2") (pintype "passive"))
      (node (ref "U2") (pin "10") (pinfunction "IO8_10") (pintype "bidirectional"))
    )
    (net (code "15") (name "I2C_PW") (class "Default")
      (node (ref "C1") (pin "1") (pinfunction "1_1") (pintype "passive"))
      (node (ref "C2") (pin "1") (pinfunction "1_1") (pintype "passive"))
      (node (ref "R1-PINH") (pin "2") (pinfunction "2_2") (pintype "passive"))
      (node (ref "R2-PINH") (pin "2") (pinfunction "2_2") (pintype "passive"))
      (node (ref "SENSOR2") (pin "2") (pinfunction "CSB_2") (pintype "input"))
      (node (ref "SENSOR2") (pin "6") (pinfunction "VDDIO_6") (pintype "power_in"))
      (node (ref "SENSOR2") (pin "8") (pinfunction "VDD_8") (pintype "power_in"))
      (node (ref "U2") (pin "17") (pinfunction "IO19_17") (pintype "bidirectional"))
    )
    (net (code "16") (name "INT_RTC") (class "Default")
      (node (ref "INT_RTC") (pin "TP") (pinfunction "TP_TP") (pintype "input"))
      (node (ref "R1-PINH1") (pin "1") (pinfunction "1_1") (pintype "passive"))
      (node (ref "U2") (pin "8") (pinfunction "IO0_8") (pintype "bidirectional"))
      (node (ref "U3") (pin "3") (pinfunction "SQW/~{INT}_3") (pintype "output"))
    )
    (net (code "17") (name "IO{slash}BOOT") (class "Default")
      (node (ref "BOOT_BUTTON") (pin "3") (pinfunction "3_3") (pintype "passive"))
      (node (ref "BOOT_BUTTON") (pin "4") (pinfunction "4_4") (pintype "passive"))
      (node (ref "C6") (pin "1") (pinfunction "1_1") (pintype "passive"))
      (node (ref "R_BOOT") (pin "2") (pinfunction "2_2") (pintype "passive"))
      (node (ref "U2") (pin "15") (pinfunction "IO9_15") (pintype "bidirectional"))
    )
    (net (code "18") (name "IO{slash}CHANGE") (class "Default")
      (node (ref "C10") (pin "1") (pinfunction "1_1") (pintype "passive"))
      (node (ref "CHANGE_BUTTON") (pin "3") (pinfunction "3_3") (pintype "passive"))
      (node (ref "CHANGE_BUTTON") (pin "4") (pinfunction "4_4") (pintype "passive"))
      (node (ref "R_CHANGE") (pin "2") (pinfunction "2_2") (pintype "passive"))
      (node (ref "U2") (pin "23") (pinfunction "IO15_23") (pintype "bidirectional"))
    )
    (net (code "19") (name "MISO") (class "Default")
      (node (ref "D12") (pin "1") (pinfunction "1_1") (pintype "passive"))
      (node (ref "J4") (pin "P7") (pinfunction "DAT0_P7") (pintype "bidirectional"))
      (node (ref "MISO") (pin "TP") (pinfunction "TP_TP") (pintype "input"))
      (node (ref "R8") (pin "1") (pinfunction "1_1") (pintype "passive"))
      (node (ref "U1") (pin "2") (pinfunction "DO(IO1)_2") (pintype "bidirectional"))
      (node (ref "U2") (pin "27") (pinfunction "IO2_27") (pintype "bidirectional"))
    )
    (net (code "20") (name "MOSI") (class "Default")
      (node (ref "D11") (pin "1") (pinfunction "1_1") (pintype "passive"))
      (node (ref "J1") (pin "14") (pinfunction "14_14") (pintype "bidirectional"))
      (node (ref "J4") (pin "P3") (pinfunction "CMD_P3") (pintype "bidirectional"))
      (node (ref "MOSI") (pin "TP") (pinfunction "TP_TP") (pintype "input"))
      (node (ref "R7") (pin "1") (pinfunction "1_1") (pintype "passive"))
      (node (ref "U1") (pin "5") (pinfunction "DI(IO0)_5") (pintype "bidirectional"))
      (node (ref "U2") (pin "7") (pinfunction "IO7_7") (pintype "bidirectional"))
    )
    (net (code "21") (name "Net-(CHG_LED-PadC)") (class "Default")
      (node (ref "CHG_LED") (pin "C") (pinfunction "C_C") (pintype "passive"))
      (node (ref "R1_BAT") (pin "2") (pinfunction "2_2") (pintype "passive"))
    )
    (net (code "22") (name "Net-(D2-CATHODE)") (class "Default")
      (node (ref "C1_BAT1") (pin "1") (pinfunction "1_1") (pintype "passive"))
      (node (ref "D2") (pin "1") (pinfunction "CATHODE_1") (pintype "bidirectional"))
      (node (ref "IC4") (pin "1") (pinfunction "VIN_1") (pintype "bidirectional"))
      (node (ref "IC4") (pin "3") (pinfunction "CE_3") (pintype "bidirectional"))
      (node (ref "Q1") (pin "2") (pinfunction "S_2") (pintype "bidirectional"))
    )
    (net (code "23") (name "Net-(D3-A)") (class "Default")
      (node (ref "C4") (pin "1") (pinfunction "1_1") (pintype "passive"))
      (node (ref "D3") (pin "2") (pinfunction "A_2") (pintype "bidirectional"))
      (node (ref "D4") (pin "1") (pinfunction "K_1") (pintype "bidirectional"))
    )
    (net (code "24") (name "Net-(D7-CATHODE)") (class "Default")
      (node (ref "D7") (pin "1") (pinfunction "CATHODE_1") (pintype "bidirectional"))
      (node (ref "R_CAPACITOR") (pin "1") (pinfunction "1_1") (pintype "passive"))
    )
    (net (code "25") (name "Net-(EPD_C1-Pad1)") (class "Default")
      (node (ref "EPD_C1") (pin "1") (pinfunction "1_1") (pintype "passive"))
      (node (ref "J1") (pin "4") (pinfunction "4_4") (pintype "bidirectional"))
    )
    (net (code "26") (name "Net-(EPD_C2-Pad1)") (class "Default")
      (node (ref "EPD_C2") (pin "1") (pinfunction "1_1") (pintype "passive"))
      (node (ref "J1") (pin "5") (pinfunction "5_5") (pintype "bidirectional"))
    )
    (net (code "27") (name "Net-(EPD_C6-Pad1)") (class "Default")
      (node (ref "EPD_C6") (pin "1") (pinfunction "1_1") (pintype "passive"))
      (node (ref "J1") (pin "18") (pinfunction "18_18") (pintype "bidirectional"))
    )
    (net (code "28") (name "Net-(EPD_C7-Pad1)") (class "Default")
      (node (ref "EPD_C7") (pin "1") (pinfunction "1_1") (pintype "passive"))
      (node (ref "J1") (pin "19") (pinfunction "19_19") (pintype "bidirectional"))
    )
    (net (code "29") (name "Net-(EPD_C8-Pad1)") (class "Default")
      (node (ref "EPD_C8") (pin "1") (pinfunction "1_1") (pintype "passive"))
      (node (ref "J1") (pin "20") (pinfunction "20_20") (pintype "bidirectional"))
    )
    (net (code "30") (name "Net-(EPD_C10-Pad1)") (class "Default")
      (node (ref "EPD_C10") (pin "1") (pinfunction "1_1") (pintype "passive"))
      (node (ref "J1") (pin "22") (pinfunction "22_22") (pintype "bidirectional"))
    )
    (net (code "31") (name "Net-(EPD_C12-Pad1)") (class "Default")
      (node (ref "EPD_C12") (pin "1") (pinfunction "1_1") (pintype "passive"))
      (node (ref "J1") (pin "24") (pinfunction "24_24") (pintype "bidirectional"))
    )
    (net (code "32") (name "Net-(IC1-CT)") (class "Default")
      (node (ref "C_DELAY") (pin "1") (pinfunction "1_1") (pintype "passive"))
      (node (ref "IC1") (pin "5") (pinfunction "CT_5") (pintype "bidirectional"))
    )
    (net (code "33") (name "Net-(J2-PadA5)") (class "Default")
      (node (ref "J2") (pin "A5") (pinfunction "A5_A5") (pintype "bidirectional"))
      (node (ref "R2-USB1") (pin "2") (pinfunction "2_2") (pintype "passive"))
    )
    (net (code "34") (name "Net-(J2-PadB5)") (class "Default")
      (node (ref "J2") (pin "B5") (pinfunction "B5_B5") (pintype "bidirectional"))
      (node (ref "R2-USB") (pin "1") (pinfunction "1_1") (pintype "passive"))
    )
    (net (code "35") (name "Net-(U5-PROG)") (class "Default")
      (node (ref "R2_BAT") (pin "2") (pinfunction "2_2") (pintype "passive"))
      (node (ref "U5") (pin "5") (pinfunction "PROG_5") (pintype "input"))
    )
    (net (code "36") (name "Net-(U5-STAT)") (class "Default")
      (node (ref "R1_BAT") (pin "1") (pinfunction "1_1") (pintype "passive"))
      (node (ref "U5") (pin "1") (pinfunction "STAT_1") (pintype "output"))
    )
    (net (code "37") (name "PREVGH") (class "Default")
      (node (ref "D5") (pin "1") (pinfunction "K_1") (pintype "bidirectional"))
      (node (ref "EPD_C9") (pin "1") (pinfunction "1_1") (pintype "passive"))
      (node (ref "J1") (pin "21") (pinfunction "21_21") (pintype "bidirectional"))
    )
    (net (code "38") (name "PREVGL") (class "Default")
      (node (ref "D4") (pin "2") (pinfunction "A_2") (pintype "bidirectional"))
      (node (ref "EPD_C11") (pin "1") (pinfunction "1_1") (pintype "passive"))
      (node (ref "J1") (pin "23") (pinfunction "23_23") (pintype "bidirectional"))
    )
    (net (code "39") (name "RESE") (class "Default")
      (node (ref "J1") (pin "3") (pinfunction "3_3") (pintype "bidirectional"))
      (node (ref "Q3") (pin "2") (pinfunction "S_2") (pintype "bidirectional"))
      (node (ref "R3") (pin "1") (pinfunction "1_1") (pintype "passive"))
    )
    (net (code "40") (name "RESE'") (class "Default")
      (node (ref "R2") (pin "2") (pinfunction "2_2") (pintype "passive"))
      (node (ref "R3") (pin "2") (pinfunction "2_2") (pintype "passive"))
      (node (ref "SJ1") (pin "2") (pinfunction "2_2") (pintype "passive"))
    )
    (net (code "41") (name "RESET") (class "Default")
      (node (ref "C5") (pin "1") (pinfunction "1_1") (pintype "passive"))
      (node (ref "IC1") (pin "1") (pinfunction "VOUT_1") (pintype "bidirectional"))
      (node (ref "RESET_BUTTON") (pin "3") (pinfunction "3_3") (pintype "passive"))
      (node (ref "RESET_BUTTON") (pin "4") (pinfunction "4_4") (pintype "passive"))
      (node (ref "R_RESET") (pin "2") (pinfunction "2_2") (pintype "passive"))
      (node (ref "U2") (pin "3") (pinfunction "EN_3") (pintype "input"))
    )
    (net (code "42") (name "RTC_RST") (class "Default")
      (node (ref "U2") (pin "16") (pinfunction "IO18_16") (pintype "bidirectional"))
      (node (ref "U3") (pin "4") (pinfunction "~{RST}_4") (pintype "input"))
    )
    (net (code "43") (name "RX") (class "Default")
      (node (ref "RX") (pin "TP") (pinfunction "TP_TP") (pintype "input"))
      (node (ref "U2") (pin "24") (pinfunction "RXD0/GPIO17_24") (pintype "bidirectional"))
    )
    (net (code "44") (name "SCK") (class "Default")
      (node (ref "D10") (pin "1") (pinfunction "1_1") (pintype "passive"))
      (node (ref "J1") (pin "13") (pinfunction "13_13") (pintype "bidirectional"))
      (node (ref "J4") (pin "P5") (pinfunction "CLK_P5") (pintype "bidirectional"))
      (node (ref "R6") (pin "1") (pinfunction "1_1") (pintype "passive"))
      (node (ref "SCK") (pin "TP") (pinfunction "TP_TP") (pintype "input"))
      (node (ref "U1") (pin "6") (pinfunction "CLK_6") (pintype "input"))
      (node (ref "U2") (pin "6") (pinfunction "IO6_6") (pintype "bidirectional"))
    )
    (net (code "45") (name "SCL") (class "Default")
      (node (ref "J3") (pin "4") (pinfunction "4_4") (pintype "passive"))
      (node (ref "R2-PINH") (pin "1") (pinfunction "1_1") (pintype "passive"))
      (node (ref "SENSOR2") (pin "4") (pinfunction "SCK_4") (pintype "input"))
      (node (ref "U2") (pin "20") (pinfunction "IO22_20") (pintype "bidirectional"))
      (node (ref "U3") (pin "16") (pinfunction "SCL_16") (pintype "input"))
      (node (ref "U4") (pin "7") (pinfunction "SCL_7") (pintype "input"))
    )
    (net (code "46") (name "SDA") (class "Default")
      (node (ref "J3") (pin "3") (pinfunction "3_3") (pintype "passive"))
      (node (ref "R1-PINH") (pin "1") (pinfunction "1_1") (pintype "passive"))
      (node (ref "SENSOR2") (pin "3") (pinfunction "SDI_3") (pintype "bidirectional"))
      (node (ref "U2") (pin "19") (pinfunction "IO21_19") (pintype "bidirectional"))
      (node (ref "U3") (pin "15") (pinfunction "SDA_15") (pintype "bidirectional"))
      (node (ref "U4") (pin "8") (pinfunction "SDA_8") (pintype "bidirectional"))
    )
    (net (code "47") (name "SRC") (class "Default")
      (node (ref "C4") (pin "2") (pinfunction "2_2") (pintype "passive"))
      (node (ref "D5") (pin "2") (pinfunction "A_2") (pintype "bidirectional"))
      (node (ref "L1") (pin "1") (pinfunction "1_1") (pintype "passive"))
      (node (ref "Q3") (pin "3") (pinfunction "D_3") (pintype "bidirectional"))
    )
    (net (code "48") (name "SS_SD") (class "Default")
      (node (ref "D8") (pin "1") (pinfunction "1_1") (pintype "passive"))
      (node (ref "J4") (pin "P2") (pinfunction "CD/DAT3_P2") (pintype "bidirectional"))
      (node (ref "R10") (pin "1") (pinfunction "1_1") (pintype "passive"))
      (node (ref "U2") (pin "4") (pinfunction "IO4_4") (pintype "bidirectional"))
    )
    (net (code "49") (name "TX") (class "Default")
      (node (ref "TX") (pin "TP") (pinfunction "TP_TP") (pintype "input"))
      (node (ref "U2") (pin "25") (pinfunction "TXD0/GPIO16_25") (pintype "bidirectional"))
    )
    (net (code "50") (name "USB_D+") (class "Default")
      (node (ref "D1") (pin "1") (pinfunction "I/O1_1_1") (pintype "bidirectional"))
      (node (ref "U2") (pin "14") (pinfunction "IO13_14") (pintype "bidirectional"))
    )
    (net (code "51") (name "USB_D-") (class "Default")
      (node (ref "D1") (pin "3") (pinfunction "I/O2_1_3") (pintype "bidirectional"))
      (node (ref "U2") (pin "13") (pinfunction "IO12_13") (pintype "bidirectional"))
    )
    (net (code "52") (name "VBAT") (class "Default")
      (node (ref "C2_BAT") (pin "1") (pinfunction "1_1") (pintype "passive"))
      (node (ref "Q1") (pin "3") (pinfunction "D_3") (pintype "bidirectional"))
      (node (ref "U4") (pin "2") (pinfunction "CELL_2") (pintype "power_in"))
      (node (ref "U4") (pin "3") (pinfunction "VDD_3") (pintype "power_in"))
      (node (ref "U5") (pin "3") (pinfunction "VBAT_3") (pintype "power_in"))
      (node (ref "VBAT") (pin "TP") (pinfunction "TP_TP") (pintype "input"))
    )
    (net (code "53") (name "VBUS") (class "Default")
      (node (ref "C1_BAT") (pin "1") (pinfunction "1_1") (pintype "passive"))
      (node (ref "C4_USB") (pin "1") (pinfunction "1_1") (pintype "passive"))
      (node (ref "C5_USB") (pin "1") (pinfunction "1_1") (pintype "passive"))
      (node (ref "CHG_LED") (pin "A") (pinfunction "A_A") (pintype "passive"))
      (node (ref "D1") (pin "5") (pinfunction "VBUS_5") (pintype "bidirectional"))
      (node (ref "D2") (pin "2") (pinfunction "ANODE_2") (pintype "bidirectional"))
      (node (ref "PFMF.050.1") (pin "2") (pinfunction "2_2") (pintype "passive"))
      (node (ref "Q1") (pin "1") (pinfunction "G_1") (pintype "bidirectional"))
      (node (ref "R1_PWRUSB") (pin "2") (pinfunction "2_2") (pintype "passive"))
      (node (ref "U5") (pin "4") (pinfunction "VIN_4") (pintype "power_in"))
      (node (ref "VBUS") (pin "TP") (pinfunction "TP_TP") (pintype "input"))
    )
    (net (code "54") (name "VRTC") (class "Default")
      (node (ref "C10_SUPERCAP") (pin "2") (pinfunction "2_2") (pintype "passive"))
      (node (ref "C8") (pin "1") (pinfunction "1_1") (pintype "passive"))
      (node (ref "R_CAPACITOR") (pin "2") (pinfunction "2_2") (pintype "passive"))
      (node (ref "U3") (pin "14") (pinfunction "VBAT_14") (pintype "power_in"))
    )
    (net (code "55") (name "VUSB") (class "Default")
      (node (ref "J2") (pin "A4") (pinfunction "A4_A4") (pintype "bidirectional"))
      (node (ref "J2") (pin "A9") (pinfunction "A9_A9") (pintype "bidirectional"))
      (node (ref "J2") (pin "B4") (pinfunction "B4_B4") (pintype "bidirectional"))
      (node (ref "J2") (pin "B9") (pinfunction "B9_B9") (pintype "bidirectional"))
      (node (ref "PFMF.050.1") (pin "1") (pinfunction "1_1") (pintype "passive"))
    )
    (net (code "56") (name "unconnected-(IC1-NC-Pad4)") (class "Default")
      (node (ref "IC1") (pin "4") (pinfunction "NC_4") (pintype "no_connect"))
    )
    (net (code "57") (name "unconnected-(IC4-NC-Pad4)") (class "Default")
      (node (ref "IC4") (pin "4") (pinfunction "NC_4") (pintype "no_connect"))
    )
    (net (code "58") (name "unconnected-(J1-Pad1)") (class "Default")
      (node (ref "J1") (pin "1") (pinfunction "1_1") (pintype "bidirectional"))
    )
    (net (code "59") (name "unconnected-(J1-Pad6)") (class "Default")
      (node (ref "J1") (pin "6") (pinfunction "6_6") (pintype "bidirectional"))
    )
    (net (code "60") (name "unconnected-(J1-Pad7)") (class "Default")
      (node (ref "J1") (pin "7") (pinfunction "7_7") (pintype "bidirectional"))
    )
    (net (code "61") (name "unconnected-(J2-PadA8)") (class "Default")
      (node (ref "J2") (pin "A8") (pinfunction "A8_A8") (pintype "bidirectional"))
    )
    (net (code "62") (name "unconnected-(J2-PadB8)") (class "Default")
      (node (ref "J2") (pin "B8") (pinfunction "B8_B8") (pintype "bidirectional"))
    )
    (net (code "63") (name "unconnected-(J4-DAT1-PadP8)") (class "Default")
      (node (ref "J4") (pin "P8") (pinfunction "DAT1_P8") (pintype "bidirectional"))
    )
    (net (code "64") (name "unconnected-(J4-DAT2-PadP1)") (class "Default")
      (node (ref "J4") (pin "P1") (pinfunction "DAT2_P1") (pintype "bidirectional"))
    )
    (net (code "65") (name "unconnected-(J4-DETECTION_1-PadS1)") (class "Default")
      (node (ref "J4") (pin "S1") (pinfunction "DETECTION_1_S1") (pintype "bidirectional"))
    )
    (net (code "66") (name "unconnected-(J4-DETECTION_2-PadS2)") (class "Default")
      (node (ref "J4") (pin "S2") (pinfunction "DETECTION_2_S2") (pintype "bidirectional"))
    )
    (net (code "67") (name "unconnected-(U2-NC-Pad22)") (class "Default")
      (node (ref "U2") (pin "22") (pinfunction "NC_22") (pintype "no_connect"))
    )
    (net (code "68") (name "unconnected-(U4-~{ALERT}-Pad5)") (class "Default")
      (node (ref "U4") (pin "5") (pinfunction "~{ALERT}_5") (pintype "output"))
    )
  )
)
